# SH1_-_POWER.net
KiCad netlist of a schematic drawn in Altium Designer
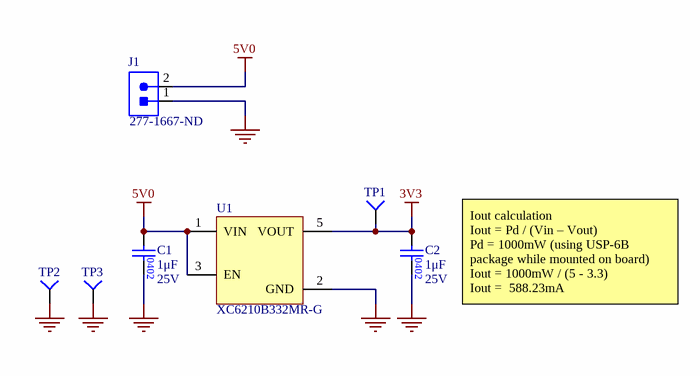
[diagram p0: SH1 - POWER.SchDoc]

(export (version "E")
  (design (tool "Eeschema 10.0.6"))
  (components
    (comp (ref "C1")
      (value "1μF")
      (footprint "CAP0402")
      (description "CAP CER 1UF 25V X5R 0402")
      (fields (field (name "VOLTAGE") "25V") (field (name "Comment") "CAP_1uF_25V_0402"))
      (libsource (lib "UWRT_Schematic_Library_2020") (part "CAP_1uF_25V_0402"))
    )
    (comp (ref "C2")
      (value "1μF")
      (footprint "CAP0402")
      (description "CAP CER 1UF 25V X5R 0402")
      (fields (field (name "VOLTAGE") "25V") (field (name "Comment") "CAP_1uF_25V_0402"))
      (libsource (lib "UWRT_Schematic_Library_2020") (part "CAP_1uF_25V_0402"))
    )
    (comp (ref "J1")
      (value "CON_2POS_SCREW_TERM")
      (footprint "1935161")
      (description "TERM BLK 2POS SIDE ENTRY 5MM")
      (fields (field (name "SUPPLIER PART NUMBER 1") "277-1667-ND"))
      (libsource (lib "UWRT_Schematic_Library_2020") (part "CON_2POS_SCREW_TERM"))
    )
    (comp (ref "TP1")
      (value "TESTPOINT_SMD_LOOP")
      (footprint "S1751-46R")
      (description "PC TEST POINT SMD")
      (libsource (lib "UWRT_Schematic_Library_2020") (part "TESTPOINT_SMD_LOOP"))
    )
    (comp (ref "TP2")
      (value "TESTPOINT_SMD_LOOP")
      (footprint "S1751-46R")
      (description "PC TEST POINT SMD")
      (libsource (lib "UWRT_Schematic_Library_2020") (part "TESTPOINT_SMD_LOOP"))
    )
    (comp (ref "TP3")
      (value "TESTPOINT_SMD_LOOP")
      (footprint "S1751-46R")
      (description "PC TEST POINT SMD")
      (libsource (lib "UWRT_Schematic_Library_2020") (part "TESTPOINT_SMD_LOOP"))
    )
    (comp (ref "U1")
      (value "LDO_3.3V_700mA")
      (footprint "SOT95P285X140-5N")
      (description "IC REG LINEAR 3.3V 700MA SOT25")
      (fields (field (name "MANUFACTURER PART NUMBER 1") "XC6210B332MR-G"))
      (libsource (lib "UWRT_Schematic_Library_2020") (part "LDO_3.3V_700mA"))
    )
  )
  (nets
    (net (code "1") (name "3V3") (class "Default")
      (node (ref "C2") (pin "1") (pinfunction "1_1") (pintype "passive"))
      (node (ref "TP1") (pin "1") (pinfunction "=value_1") (pintype "passive"))
      (node (ref "U1") (pin "5") (pinfunction "VOUT_5") (pintype "passive"))
    )
    (net (code "2") (name "5V0") (class "Default")
      (node (ref "C1") (pin "1") (pinfunction "1_1") (pintype "passive"))
      (node (ref "J1") (pin "2") (pinfunction "2_2") (pintype "passive"))
      (node (ref "U1") (pin "1") (pinfunction "VIN_1") (pintype "passive"))
      (node (ref "U1") (pin "3") (pinfunction "EN_3") (pintype "passive"))
    )
    (net (code "3") (name "GND") (class "Default")
      (node (ref "C1") (pin "2") (pinfunction "2_2") (pintype "passive"))
      (node (ref "C2") (pin "2") (pinfunction "2_2") (pintype "passive"))
      (node (ref "J1") (pin "1") (pinfunction "1_1") (pintype "passive"))
      (node (ref "TP2") (pin "1") (pinfunction "=value_1") (pintype "passive"))
      (node (ref "TP3") (pin "1") (pinfunction "=value_1") (pintype "passive"))
      (node (ref "U1") (pin "2") (pinfunction "GND_2") (pintype "passive"))
    )
  )
)
